# Shared_IoT_Dev.net
KiCad netlist of a schematic drawn in Altium Designer
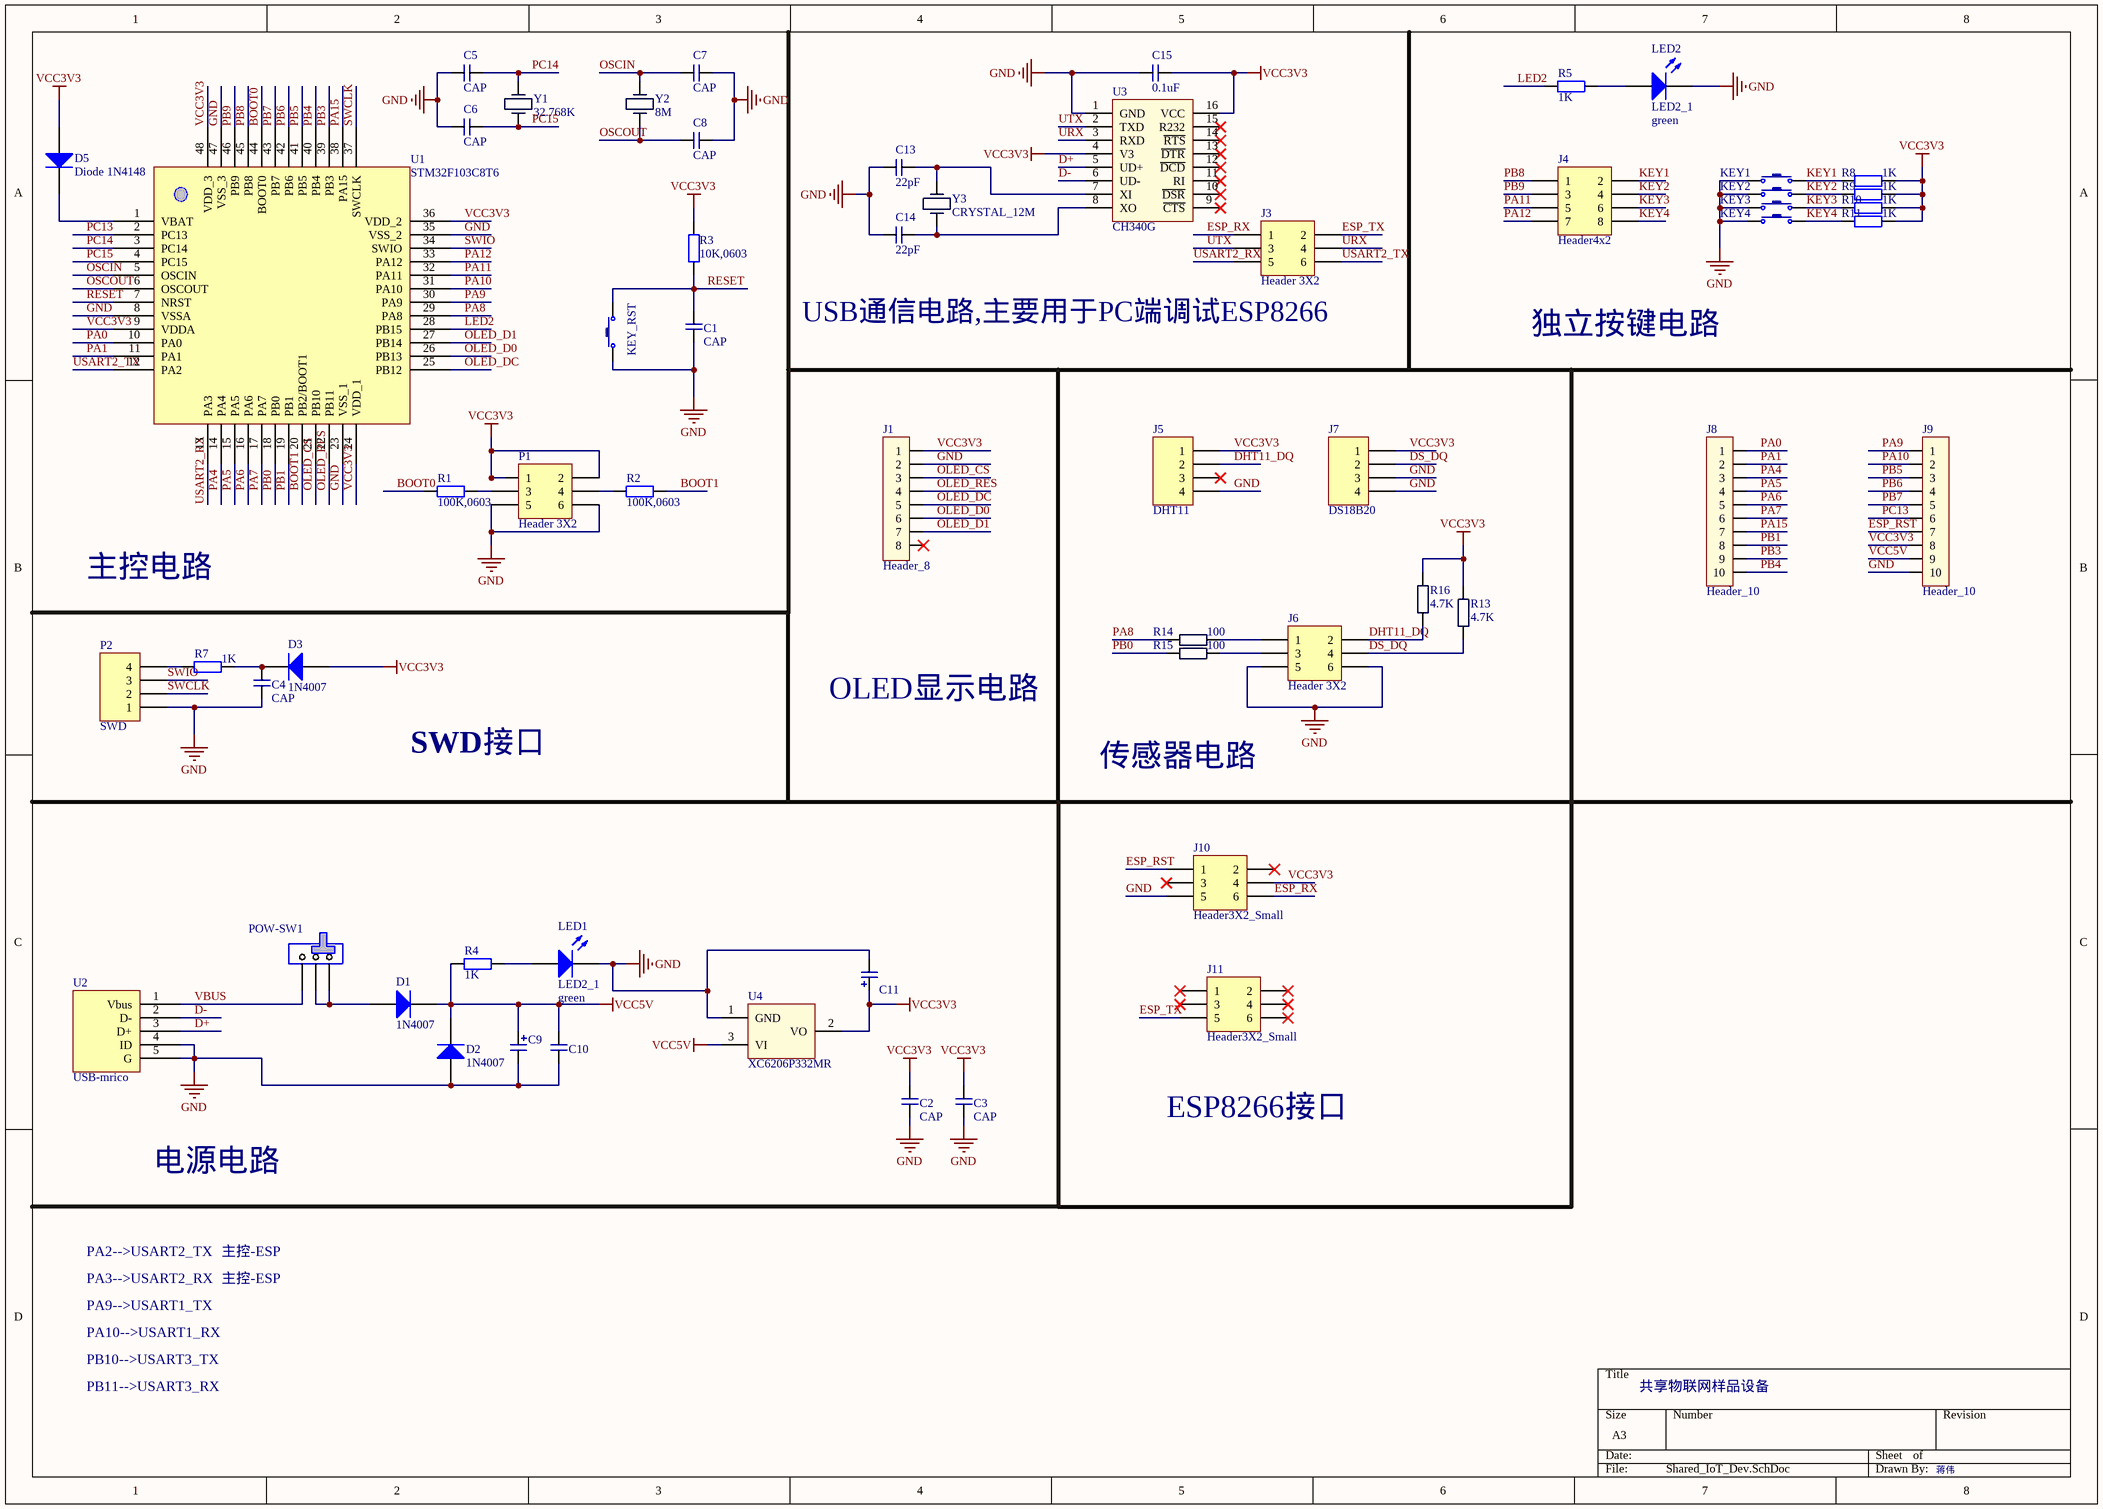
[diagram p0: Shared_IoT_Dev.SchDoc]

(export (version "E")
  (design (tool "Eeschema 10.0.6"))
  (components
    (comp (ref "C1") (value "CAP") (footprint "C0805") (libsource (lib "Arduino") (part "CAP")))
    (comp (ref "C2") (value "CAP") (footprint "C0805") (libsource (lib "Arduino") (part "CAP")))
    (comp (ref "C3") (value "CAP") (footprint "C0805") (libsource (lib "Arduino") (part "CAP")))
    (comp (ref "C4") (value "CAP") (footprint "C0805") (libsource (lib "Arduino") (part "CAP")))
    (comp (ref "C5") (value "CAP") (footprint "C0805") (libsource (lib "Arduino") (part "CAP")))
    (comp (ref "C6") (value "CAP") (footprint "C0805") (libsource (lib "Arduino") (part "CAP")))
    (comp (ref "C7") (value "CAP") (footprint "C0805") (libsource (lib "Arduino") (part "CAP")))
    (comp (ref "C8") (value "CAP") (footprint "C0805") (libsource (lib "Arduino") (part "CAP")))
    (comp (ref "C9") (value "CAP_POL") (footprint "CAP-TH_POL") (libsource (lib "Arduino") (part "CAP_POL")))
    (comp (ref "C10") (value "CAP") (footprint "C0805") (libsource (lib "Arduino") (part "CAP")))
    (comp (ref "C11") (value "CAP_POL") (footprint "CAP-TH_POL") (libsource (lib "Arduino") (part "CAP_POL")))
    (comp (ref "C13")
      (value "22pF")
      (footprint "C0805")
      (description "CAP")
      (libsource (lib "Arduino") (part "CAP"))
    )
    (comp (ref "C14")
      (value "22pF")
      (footprint "C0805")
      (description "CAP")
      (libsource (lib "Arduino") (part "CAP"))
    )
    (comp (ref "C15")
      (value "0.1uF")
      (footprint "C0805")
      (description "CAP")
      (libsource (lib "Arduino") (part "CAP"))
    )
    (comp (ref "D1") (value "1N4007") (footprint "SMA") (libsource (lib "电流测量仪仪主控板原理图7950") (part "DIODE")))
    (comp (ref "D2") (value "1N4007") (footprint "SMA") (libsource (lib "电流测量仪仪主控板原理图7950") (part "DIODE")))
    (comp (ref "D3") (value "1N4007") (footprint "SMA") (libsource (lib "电流测量仪仪主控板原理图7950") (part "DIODE")))
    (comp (ref "D5")
      (value "Diode 1N4148")
      (footprint "SMA")
      (description "High Conductance Fast Diode")
      (fields (field (name "PUBLISHER") "Altium Limited"))
      (libsource (lib "电流测量仪仪主控板原理图7950") (part "Diode 1N4148"))
    )
    (comp (ref "J1")
      (value "Header_8")
      (footprint "HDR-TH_8P-P2.54-V")
      (libsource (lib "Arduino") (part "Header_8"))
    )
    (comp (ref "J3")
      (value "Header 3X2")
      (footprint "HDR2X3")
      (description "Header, 3-Pin, Dual row")
      (fields (field (name "PUBLISHER") "Altium Limited"))
      (libsource (lib "STM32F103C8T6") (part "Header 3X2"))
    )
    (comp (ref "J4")
      (value "Header4x2")
      (footprint "HDR2X4")
      (libsource (lib "STM32F103C8T6") (part "Header4x2"))
    )
    (comp (ref "J5")
      (value "DHT11")
      (footprint "HDR1X4H")
      (description "Header, 4-Pin")
      (fields (field (name "PUBLISHER") "Altium Limited"))
      (libsource (lib "STM32F103C8T6") (part "Header 4"))
    )
    (comp (ref "J6")
      (value "Header 3X2")
      (footprint "HDR2X3")
      (description "Header, 3-Pin, Dual row")
      (fields (field (name "PUBLISHER") "Altium Limited"))
      (libsource (lib "STM32F103C8T6") (part "Header 3X2"))
    )
    (comp (ref "J7")
      (value "DS18B20")
      (footprint "HDR1X4H")
      (description "Header, 4-Pin")
      (fields (field (name "PUBLISHER") "Altium Limited"))
      (libsource (lib "STM32F103C8T6") (part "Header 4"))
    )
    (comp (ref "J8")
      (value "Header_10")
      (footprint "HDR-TH_10P-P2.54-V")
      (libsource (lib "Arduino") (part "Header_10"))
    )
    (comp (ref "J9")
      (value "Header_10")
      (footprint "HDR-TH_10P-P2.54-V")
      (libsource (lib "") (part "Header_10_1"))
    )
    (comp (ref "J10")
      (value "Header3X2_Small")
      (footprint "HDR3X2_Small")
      (libsource (lib "STM32F103C8T6") (part "Header3X2_Small"))
    )
    (comp (ref "J11")
      (value "Header3X2_Small")
      (footprint "HDR3X2_Small")
      (libsource (lib "STM32F103C8T6") (part "Header3X2_Small"))
    )
    (comp (ref "KEY1") (value "KEY") (footprint "KEY-TH_4P") (libsource (lib "Arduino") (part "KEY")))
    (comp (ref "KEY2") (value "KEY") (footprint "KEY-TH_4P") (libsource (lib "Arduino") (part "KEY")))
    (comp (ref "KEY3") (value "KEY") (footprint "KEY-TH_4P") (libsource (lib "Arduino") (part "KEY")))
    (comp (ref "KEY4") (value "KEY") (footprint "KEY-TH_4P") (libsource (lib "Arduino") (part "KEY")))
    (comp (ref "KEY_RST") (value "KEY") (footprint "KEY-TH_4P") (libsource (lib "Arduino") (part "KEY")))
    (comp (ref "LED1")
      (value "LED2_1")
      (footprint "0805C")
      (description "Typical RED, GREEN, YELLOW, AMBER GaAs LED")
      (fields (field (name "ALTIUM_UNNAMED_1") "green") (field (name "PUBLISHER") "Altium Limited"))
      (libsource (lib "电流测量仪仪主控板原理图7950") (part "LED2_1"))
    )
    (comp (ref "LED2")
      (value "LED2_1")
      (footprint "0805C")
      (description "Typical RED, GREEN, YELLOW, AMBER GaAs LED")
      (fields (field (name "ALTIUM_UNNAMED_1") "green") (field (name "PUBLISHER") "Altium Limited"))
      (libsource (lib "电流测量仪仪主控板原理图7950") (part "LED2_1"))
    )
    (comp (ref "P1")
      (value "Header 3X2")
      (footprint "HDR2X3")
      (description "Header, 3-Pin, Dual row")
      (fields (field (name "PUBLISHER") "Altium Limited"))
      (libsource (lib "STM32F103C8T6") (part "Header 3X2"))
    )
    (comp (ref "P2")
      (value "SWD")
      (footprint "HDR1X4H")
      (description "Header, 4-Pin")
      (fields (field (name "PUBLISHER") "Altium Limited"))
      (libsource (lib "") (part "Header 4_1"))
    )
    (comp (ref "POW-SW1")
      (value "Switch")
      (footprint "SW")
      (libsource (lib "电流测量仪仪主控板原理图7950") (part "Swich_On_Off"))
    )
    (comp (ref "R1")
      (value "100K,0603")
      (footprint "R0805")
      (description "Resistor")
      (fields (field (name "PUBLISHER") "Altium Limited"))
      (libsource (lib "") (part "Res2_1"))
    )
    (comp (ref "R2")
      (value "100K,0603")
      (footprint "R0805")
      (description "Resistor")
      (fields (field (name "PUBLISHER") "Altium Limited"))
      (libsource (lib "") (part "Res2_1"))
    )
    (comp (ref "R3")
      (value "10K,0603")
      (footprint "R0805")
      (description "Resistor")
      (fields (field (name "PUBLISHER") "Altium Limited"))
      (libsource (lib "STM32F103C8T6") (part "Res2"))
    )
    (comp (ref "R4")
      (value "1K")
      (footprint "0805R")
      (description "Resistor")
      (fields (field (name "Comment") "Res2") (field (name "PUBLISHER") "Altium Limited"))
      (libsource (lib "电流测量仪仪主控板原理图7950") (part "Res_3"))
    )
    (comp (ref "R5")
      (value "1K")
      (footprint "0805R")
      (description "Resistor")
      (fields (field (name "Comment") "Res2") (field (name "PUBLISHER") "Altium Limited"))
      (libsource (lib "电流测量仪仪主控板原理图7950") (part "Res_3"))
    )
    (comp (ref "R7")
      (value "1K")
      (footprint "0805R")
      (description "Resistor")
      (fields (field (name "Comment") "Res2") (field (name "PUBLISHER") "Altium Limited"))
      (libsource (lib "电流测量仪仪主控板原理图7950") (part "Res2"))
    )
    (comp (ref "R8")
      (value "1K")
      (footprint "0805R")
      (description "Resistor")
      (fields (field (name "Comment") "Res2") (field (name "PUBLISHER") "Altium Limited"))
      (libsource (lib "电流测量仪仪主控板原理图7950") (part "Res_3"))
    )
    (comp (ref "R9")
      (value "1K")
      (footprint "0805R")
      (description "Resistor")
      (fields (field (name "Comment") "Res2") (field (name "PUBLISHER") "Altium Limited"))
      (libsource (lib "电流测量仪仪主控板原理图7950") (part "Res_3"))
    )
    (comp (ref "R10")
      (value "1K")
      (footprint "0805R")
      (description "Resistor")
      (fields (field (name "Comment") "Res2") (field (name "PUBLISHER") "Altium Limited"))
      (libsource (lib "电流测量仪仪主控板原理图7950") (part "Res_3"))
    )
    (comp (ref "R11")
      (value "1K")
      (footprint "0805R")
      (description "Resistor")
      (fields (field (name "Comment") "Res2") (field (name "PUBLISHER") "Altium Limited"))
      (libsource (lib "电流测量仪仪主控板原理图7950") (part "Res_3"))
    )
    (comp (ref "R13")
      (value "4.7K")
      (footprint "R0805")
      (description "RES")
      (libsource (lib "Arduino") (part "RES"))
    )
    (comp (ref "R14")
      (value "100")
      (footprint "R0805")
      (description "RES")
      (libsource (lib "Arduino") (part "RES"))
    )
    (comp (ref "R15")
      (value "100")
      (footprint "R0805")
      (description "RES")
      (libsource (lib "Arduino") (part "RES"))
    )
    (comp (ref "R16")
      (value "4.7K")
      (footprint "R0805")
      (description "RES")
      (libsource (lib "Arduino") (part "RES"))
    )
    (comp (ref "U1")
      (value "STM32F103C8T6")
      (footprint "48P")
      (libsource (lib "STM32F103C8T6") (part "STM32F103C8T6"))
    )
    (comp (ref "U2")
      (value "USB-mrico")
      (footprint "Micro_USB")
      (libsource (lib "STM32F103C8T6") (part "usb-STM"))
    )
    (comp (ref "U3") (value "CH340G") (footprint "CH340G_SOIC") (libsource (lib "Arduino") (part "CH340G")))
    (comp (ref "U4")
      (value "XC6206P332MR")
      (footprint "XC_SOT-23-3")
      (description "XC6206P332MR Power Lower to 3.3v")
      (libsource (lib "Arduino") (part "XC6206P332MR"))
    )
    (comp (ref "Y1")
      (value "32.768K")
      (footprint "CRYSTAL")
      (description "CRYSTAL")
      (libsource (lib "Arduino") (part "CRYSTAL"))
    )
    (comp (ref "Y2")
      (value "8M")
      (footprint "CRYSTAL")
      (description "CRYSTAL")
      (libsource (lib "Arduino") (part "CRYSTAL"))
    )
    (comp (ref "Y3")
      (value "CRYSTAL_12M")
      (footprint "CRYSTAL")
      (description "CRYSTAL")
      (libsource (lib "Arduino") (part "CRYSTAL"))
    )
  )
  (nets
    (net (code "1") (name "/BOOT0") (class "Default")
      (node (ref "R1") (pin "1") (pinfunction "1_1") (pintype "passive"))
      (node (ref "U1") (pin "44") (pinfunction "BOOT0_44") (pintype "passive"))
    )
    (net (code "2") (name "/BOOT1") (class "Default")
      (node (ref "R2") (pin "2") (pinfunction "2_2") (pintype "passive"))
      (node (ref "U1") (pin "20") (pinfunction "PB2/BOOT1_20") (pintype "passive"))
    )
    (net (code "3") (name "/D+") (class "Default")
      (node (ref "U2") (pin "3") (pinfunction "D+_3") (pintype "passive"))
      (node (ref "U3") (pin "5") (pinfunction "UD+_5") (pintype "passive"))
    )
    (net (code "4") (name "/D-") (class "Default")
      (node (ref "U2") (pin "2") (pinfunction "D-_2") (pintype "passive"))
      (node (ref "U3") (pin "6") (pinfunction "UD-_6") (pintype "passive"))
    )
    (net (code "5") (name "/DHT11_DQ") (class "Default")
      (node (ref "J5") (pin "2") (pinfunction "2_2") (pintype "passive"))
      (node (ref "J6") (pin "2") (pinfunction "2_2") (pintype "passive"))
      (node (ref "R16") (pin "1") (pinfunction "1_1") (pintype "passive"))
    )
    (net (code "6") (name "/DS_DQ") (class "Default")
      (node (ref "J6") (pin "4") (pinfunction "4_4") (pintype "passive"))
      (node (ref "J7") (pin "2") (pinfunction "2_2") (pintype "passive"))
      (node (ref "R13") (pin "1") (pinfunction "1_1") (pintype "passive"))
    )
    (net (code "7") (name "/ESP_RST") (class "Default")
      (node (ref "J10") (pin "1") (pinfunction "1_1") (pintype "passive"))
      (node (ref "J9") (pin "7") (pinfunction "7_7") (pintype "passive"))
    )
    (net (code "8") (name "/ESP_RX") (class "Default")
      (node (ref "J10") (pin "6") (pinfunction "6_6") (pintype "passive"))
      (node (ref "J3") (pin "1") (pinfunction "1_1") (pintype "passive"))
    )
    (net (code "9") (name "/ESP_TX") (class "Default")
      (node (ref "J11") (pin "5") (pinfunction "5_5") (pintype "passive"))
      (node (ref "J3") (pin "2") (pinfunction "2_2") (pintype "passive"))
    )
    (net (code "10") (name "/KEY1") (class "Default")
      (node (ref "J4") (pin "2") (pinfunction "2_2") (pintype "passive"))
      (node (ref "KEY1") (pin "3") (pinfunction "3_3") (pintype "passive"))
      (node (ref "R8") (pin "1") (pinfunction "1_1") (pintype "passive"))
    )
    (net (code "11") (name "/KEY2") (class "Default")
      (node (ref "J4") (pin "4") (pinfunction "4_4") (pintype "passive"))
      (node (ref "KEY2") (pin "3") (pinfunction "3_3") (pintype "passive"))
      (node (ref "R9") (pin "1") (pinfunction "1_1") (pintype "passive"))
    )
    (net (code "12") (name "/KEY3") (class "Default")
      (node (ref "J4") (pin "6") (pinfunction "6_6") (pintype "passive"))
      (node (ref "KEY3") (pin "3") (pinfunction "3_3") (pintype "passive"))
      (node (ref "R10") (pin "1") (pinfunction "1_1") (pintype "passive"))
    )
    (net (code "13") (name "/KEY4") (class "Default")
      (node (ref "J4") (pin "8") (pinfunction "8_8") (pintype "passive"))
      (node (ref "KEY4") (pin "3") (pinfunction "3_3") (pintype "passive"))
      (node (ref "R11") (pin "1") (pinfunction "1_1") (pintype "passive"))
    )
    (net (code "14") (name "/LED2") (class "Default")
      (node (ref "R5") (pin "1") (pinfunction "1_1") (pintype "passive"))
      (node (ref "U1") (pin "28") (pinfunction "PB15_28") (pintype "passive"))
    )
    (net (code "15") (name "/OLED_CS") (class "Default")
      (node (ref "J1") (pin "3") (pinfunction "3_3") (pintype "passive"))
      (node (ref "U1") (pin "21") (pinfunction "PB10_21") (pintype "passive"))
    )
    (net (code "16") (name "/OLED_D0") (class "Default")
      (node (ref "J1") (pin "6") (pinfunction "6_6") (pintype "passive"))
      (node (ref "U1") (pin "26") (pinfunction "PB13_26") (pintype "passive"))
    )
    (net (code "17") (name "/OLED_D1") (class "Default")
      (node (ref "J1") (pin "7") (pinfunction "7_7") (pintype "passive"))
      (node (ref "U1") (pin "27") (pinfunction "PB14_27") (pintype "passive"))
    )
    (net (code "18") (name "/OLED_DC") (class "Default")
      (node (ref "J1") (pin "5") (pinfunction "5_5") (pintype "passive"))
      (node (ref "U1") (pin "25") (pinfunction "PB12_25") (pintype "passive"))
    )
    (net (code "19") (name "/OLED_RES") (class "Default")
      (node (ref "J1") (pin "4") (pinfunction "4_4") (pintype "passive"))
      (node (ref "U1") (pin "22") (pinfunction "PB11_22") (pintype "passive"))
    )
    (net (code "20") (name "/OSCIN") (class "Default")
      (node (ref "C7") (pin "1") (pinfunction "1_1") (pintype "passive"))
      (node (ref "U1") (pin "5") (pinfunction "OSCIN_5") (pintype "passive"))
      (node (ref "Y2") (pin "2") (pinfunction "2_2") (pintype "passive"))
    )
    (net (code "21") (name "/OSCOUT") (class "Default")
      (node (ref "C8") (pin "1") (pinfunction "1_1") (pintype "passive"))
      (node (ref "U1") (pin "6") (pinfunction "OSCOUT_6") (pintype "passive"))
      (node (ref "Y2") (pin "1") (pinfunction "1_1") (pintype "passive"))
    )
    (net (code "22") (name "/PA0") (class "Default")
      (node (ref "J8") (pin "1") (pinfunction "1_1") (pintype "passive"))
      (node (ref "U1") (pin "10") (pinfunction "PA0_10") (pintype "passive"))
    )
    (net (code "23") (name "/PA1") (class "Default")
      (node (ref "J8") (pin "2") (pinfunction "2_2") (pintype "passive"))
      (node (ref "U1") (pin "11") (pinfunction "PA1_11") (pintype "passive"))
    )
    (net (code "24") (name "/PA4") (class "Default")
      (node (ref "J8") (pin "3") (pinfunction "3_3") (pintype "passive"))
      (node (ref "U1") (pin "14") (pinfunction "PA4_14") (pintype "passive"))
    )
    (net (code "25") (name "/PA5") (class "Default")
      (node (ref "J8") (pin "4") (pinfunction "4_4") (pintype "passive"))
      (node (ref "U1") (pin "15") (pinfunction "PA5_15") (pintype "passive"))
    )
    (net (code "26") (name "/PA6") (class "Default")
      (node (ref "J8") (pin "5") (pinfunction "5_5") (pintype "passive"))
      (node (ref "U1") (pin "16") (pinfunction "PA6_16") (pintype "passive"))
    )
    (net (code "27") (name "/PA7") (class "Default")
      (node (ref "J8") (pin "6") (pinfunction "6_6") (pintype "passive"))
      (node (ref "U1") (pin "17") (pinfunction "PA7_17") (pintype "passive"))
    )
    (net (code "28") (name "/PA8") (class "Default")
      (node (ref "R14") (pin "2") (pinfunction "2_2") (pintype "passive"))
      (node (ref "U1") (pin "29") (pinfunction "PA8_29") (pintype "passive"))
    )
    (net (code "29") (name "/PA9") (class "Default")
      (node (ref "J9") (pin "1") (pinfunction "1_1") (pintype "passive"))
      (node (ref "U1") (pin "30") (pinfunction "PA9_30") (pintype "passive"))
    )
    (net (code "30") (name "/PA10") (class "Default")
      (node (ref "J9") (pin "2") (pinfunction "2_2") (pintype "passive"))
      (node (ref "U1") (pin "31") (pinfunction "PA10_31") (pintype "passive"))
    )
    (net (code "31") (name "/PA11") (class "Default")
      (node (ref "J4") (pin "5") (pinfunction "5_5") (pintype "passive"))
      (node (ref "U1") (pin "32") (pinfunction "PA11_32") (pintype "passive"))
    )
    (net (code "32") (name "/PA12") (class "Default")
      (node (ref "J4") (pin "7") (pinfunction "7_7") (pintype "passive"))
      (node (ref "U1") (pin "33") (pinfunction "PA12_33") (pintype "passive"))
    )
    (net (code "33") (name "/PA15") (class "Default")
      (node (ref "J8") (pin "7") (pinfunction "7_7") (pintype "passive"))
      (node (ref "U1") (pin "38") (pinfunction "PA15_38") (pintype "passive"))
    )
    (net (code "34") (name "/PB0") (class "Default")
      (node (ref "R15") (pin "2") (pinfunction "2_2") (pintype "passive"))
      (node (ref "U1") (pin "18") (pinfunction "PB0_18") (pintype "passive"))
    )
    (net (code "35") (name "/PB1") (class "Default")
      (node (ref "J8") (pin "8") (pinfunction "8_8") (pintype "passive"))
      (node (ref "U1") (pin "19") (pinfunction "PB1_19") (pintype "passive"))
    )
    (net (code "36") (name "/PB3") (class "Default")
      (node (ref "J8") (pin "9") (pinfunction "9_9") (pintype "passive"))
      (node (ref "U1") (pin "39") (pinfunction "PB3_39") (pintype "passive"))
    )
    (net (code "37") (name "/PB4") (class "Default")
      (node (ref "J8") (pin "10") (pinfunction "10_10") (pintype "passive"))
      (node (ref "U1") (pin "40") (pinfunction "PB4_40") (pintype "passive"))
    )
    (net (code "38") (name "/PB5") (class "Default")
      (node (ref "J9") (pin "3") (pinfunction "3_3") (pintype "passive"))
      (node (ref "U1") (pin "41") (pinfunction "PB5_41") (pintype "passive"))
    )
    (net (code "39") (name "/PB6") (class "Default")
      (node (ref "J9") (pin "4") (pinfunction "4_4") (pintype "passive"))
      (node (ref "U1") (pin "42") (pinfunction "PB6_42") (pintype "passive"))
    )
    (net (code "40") (name "/PB7") (class "Default")
      (node (ref "J9") (pin "5") (pinfunction "5_5") (pintype "passive"))
      (node (ref "U1") (pin "43") (pinfunction "PB7_43") (pintype "passive"))
    )
    (net (code "41") (name "/PB8") (class "Default")
      (node (ref "J4") (pin "1") (pinfunction "1_1") (pintype "passive"))
      (node (ref "U1") (pin "45") (pinfunction "PB8_45") (pintype "passive"))
    )
    (net (code "42") (name "/PB9") (class "Default")
      (node (ref "J4") (pin "3") (pinfunction "3_3") (pintype "passive"))
      (node (ref "U1") (pin "46") (pinfunction "PB9_46") (pintype "passive"))
    )
    (net (code "43") (name "/PC13") (class "Default")
      (node (ref "J9") (pin "6") (pinfunction "6_6") (pintype "passive"))
      (node (ref "U1") (pin "2") (pinfunction "PC13_2") (pintype "passive"))
    )
    (net (code "44") (name "/PC14") (class "Default")
      (node (ref "C5") (pin "2") (pinfunction "2_2") (pintype "passive"))
      (node (ref "U1") (pin "3") (pinfunction "PC14_3") (pintype "passive"))
      (node (ref "Y1") (pin "2") (pinfunction "2_2") (pintype "passive"))
    )
    (net (code "45") (name "/PC15") (class "Default")
      (node (ref "C6") (pin "2") (pinfunction "2_2") (pintype "passive"))
      (node (ref "U1") (pin "4") (pinfunction "PC15_4") (pintype "passive"))
      (node (ref "Y1") (pin "1") (pinfunction "1_1") (pintype "passive"))
    )
    (net (code "46") (name "/RESET") (class "Default")
      (node (ref "C1") (pin "1") (pinfunction "1_1") (pintype "passive"))
      (node (ref "KEY_RST") (pin "3") (pinfunction "3_3") (pintype "passive"))
      (node (ref "R3") (pin "1") (pinfunction "1_1") (pintype "passive"))
      (node (ref "U1") (pin "7") (pinfunction "NRST_7") (pintype "passive"))
    )
    (net (code "47") (name "/SWCLK") (class "Default")
      (node (ref "P2") (pin "2") (pinfunction "2_2") (pintype "passive"))
      (node (ref "U1") (pin "37") (pinfunction "SWCLK_37") (pintype "passive"))
    )
    (net (code "48") (name "/SWIO") (class "Default")
      (node (ref "P2") (pin "3") (pinfunction "3_3") (pintype "passive"))
      (node (ref "U1") (pin "34") (pinfunction "SWIO_34") (pintype "passive"))
    )
    (net (code "49") (name "/URX") (class "Default")
      (node (ref "J3") (pin "4") (pinfunction "4_4") (pintype "passive"))
      (node (ref "U3") (pin "3") (pinfunction "RXD_3") (pintype "passive"))
    )
    (net (code "50") (name "/USART2_RX") (class "Default")
      (node (ref "J3") (pin "5") (pinfunction "5_5") (pintype "passive"))
      (node (ref "U1") (pin "13") (pinfunction "PA3_13") (pintype "passive"))
    )
    (net (code "51") (name "/USART2_TX") (class "Default")
      (node (ref "J3") (pin "6") (pinfunction "6_6") (pintype "passive"))
      (node (ref "U1") (pin "12") (pinfunction "PA2_12") (pintype "passive"))
    )
    (net (code "52") (name "/UTX") (class "Default")
      (node (ref "J3") (pin "3") (pinfunction "3_3") (pintype "passive"))
      (node (ref "U3") (pin "2") (pinfunction "TXD_2") (pintype "passive"))
    )
    (net (code "53") (name "/VBUS") (class "Default")
      (node (ref "POW-SW1") (pin "1") (pinfunction "1_1") (pintype "passive"))
      (node (ref "U2") (pin "1") (pinfunction "Vbus_1") (pintype "passive"))
    )
    (net (code "54") (name "GND") (class "Default")
      (node (ref "C1") (pin "2") (pinfunction "2_2") (pintype "passive"))
      (node (ref "C10") (pin "1") (pinfunction "1_1") (pintype "passive"))
      (node (ref "C11") (pin "2") (pinfunction "2_2") (pintype "passive"))
      (node (ref "C13") (pin "2") (pinfunction "2_2") (pintype "passive"))
      (node (ref "C14") (pin "2") (pinfunction "2_2") (pintype "passive"))
      (node (ref "C15") (pin "2") (pinfunction "2_2") (pintype "passive"))
      (node (ref "C2") (pin "2") (pinfunction "2_2") (pintype "passive"))
      (node (ref "C3") (pin "2") (pinfunction "2_2") (pintype "passive"))
      (node (ref "C4") (pin "2") (pinfunction "2_2") (pintype "passive"))
      (node (ref "C5") (pin "1") (pinfunction "1_1") (pintype "passive"))
      (node (ref "C6") (pin "1") (pinfunction "1_1") (pintype "passive"))
      (node (ref "C7") (pin "2") (pinfunction "2_2") (pintype "passive"))
      (node (ref "C8") (pin "2") (pinfunction "2_2") (pintype "passive"))
      (node (ref "C9") (pin "2") (pinfunction "2_2") (pintype "passive"))
      (node (ref "D2") (pin "1") (pinfunction "A_1") (pintype "passive"))
      (node (ref "J1") (pin "2") (pinfunction "2_2") (pintype "passive"))
      (node (ref "J10") (pin "5") (pinfunction "5_5") (pintype "passive"))
      (node (ref "J5") (pin "4") (pinfunction "4_4") (pintype "passive"))
      (node (ref "J6") (pin "5") (pinfunction "5_5") (pintype "passive"))
      (node (ref "J6") (pin "6") (pinfunction "6_6") (pintype "passive"))
      (node (ref "J7") (pin "3") (pinfunction "3_3") (pintype "passive"))
      (node (ref "J7") (pin "4") (pinfunction "4_4") (pintype "passive"))
      (node (ref "J9") (pin "10") (pinfunction "10_10") (pintype "passive"))
      (node (ref "KEY1") (pin "1") (pinfunction "1_1") (pintype "passive"))
      (node (ref "KEY2") (pin "1") (pinfunction "1_1") (pintype "passive"))
      (node (ref "KEY3") (pin "1") (pinfunction "1_1") (pintype "passive"))
      (node (ref "KEY4") (pin "1") (pinfunction "1_1") (pintype "passive"))
      (node (ref "KEY_RST") (pin "1") (pinfunction "1_1") (pintype "passive"))
      (node (ref "LED1") (pin "2") (pinfunction "K_2") (pintype "passive"))
      (node (ref "LED2") (pin "2") (pinfunction "K_2") (pintype "passive"))
      (node (ref "P1") (pin "5") (pinfunction "5_5") (pintype "passive"))
      (node (ref "P1") (pin "6") (pinfunction "6_6") (pintype "passive"))
      (node (ref "P2") (pin "1") (pinfunction "1_1") (pintype "passive"))
      (node (ref "U1") (pin "23") (pinfunction "VSS_1_23") (pintype "passive"))
      (node (ref "U1") (pin "35") (pinfunction "VSS_2_35") (pintype "passive"))
      (node (ref "U1") (pin "47") (pinfunction "VSS_3_47") (pintype "passive"))
      (node (ref "U1") (pin "8") (pinfunction "VSSA_8") (pintype "passive"))
      (node (ref "U2") (pin "4") (pinfunction "ID_4") (pintype "passive"))
      (node (ref "U2") (pin "5") (pinfunction "G_5") (pintype "passive"))
      (node (ref "U3") (pin "1") (pinfunction "GND_1") (pintype "passive"))
      (node (ref "U4") (pin "1") (pinfunction "GND_1") (pintype "passive"))
    )
    (net (code "55") (name "Net-(D1-A)") (class "Default")
      (node (ref "D1") (pin "1") (pinfunction "A_1") (pintype "passive"))
      (node (ref "POW-SW1") (pin "2") (pinfunction "2_2") (pintype "passive"))
      (node (ref "POW-SW1") (pin "3") (pinfunction "3_3") (pintype "passive"))
    )
    (net (code "56") (name "Net-(D3-K)") (class "Default")
      (node (ref "C4") (pin "1") (pinfunction "1_1") (pintype "passive"))
      (node (ref "D3") (pin "2") (pinfunction "K_2") (pintype "passive"))
      (node (ref "R7") (pin "2") (pinfunction "2_2") (pintype "passive"))
    )
    (net (code "57") (name "Net-(D5-K)") (class "Default")
      (node (ref "D5") (pin "2") (pinfunction "K_2") (pintype "passive"))
      (node (ref "U1") (pin "1") (pinfunction "VBAT_1") (pintype "passive"))
    )
    (net (code "58") (name "Net-(J6-Pad1)") (class "Default")
      (node (ref "J6") (pin "1") (pinfunction "1_1") (pintype "passive"))
      (node (ref "R14") (pin "1") (pinfunction "1_1") (pintype "passive"))
    )
    (net (code "59") (name "Net-(J6-Pad3)") (class "Default")
      (node (ref "J6") (pin "3") (pinfunction "3_3") (pintype "passive"))
      (node (ref "R15") (pin "1") (pinfunction "1_1") (pintype "passive"))
    )
    (net (code "60") (name "Net-(LED1-A)") (class "Default")
      (node (ref "LED1") (pin "1") (pinfunction "A_1") (pintype "passive"))
      (node (ref "R4") (pin "2") (pinfunction "2_2") (pintype "passive"))
    )
    (net (code "61") (name "Net-(LED2-A)") (class "Default")
      (node (ref "LED2") (pin "1") (pinfunction "A_1") (pintype "passive"))
      (node (ref "R5") (pin "2") (pinfunction "2_2") (pintype "passive"))
    )
    (net (code "62") (name "Net-(P1-Pad3)") (class "Default")
      (node (ref "P1") (pin "3") (pinfunction "3_3") (pintype "passive"))
      (node (ref "R1") (pin "2") (pinfunction "2_2") (pintype "passive"))
    )
    (net (code "63") (name "Net-(P1-Pad4)") (class "Default")
      (node (ref "P1") (pin "4") (pinfunction "4_4") (pintype "passive"))
      (node (ref "R2") (pin "1") (pinfunction "1_1") (pintype "passive"))
    )
    (net (code "64") (name "Net-(P2-Pad4)") (class "Default")
      (node (ref "P2") (pin "4") (pinfunction "4_4") (pintype "passive"))
      (node (ref "R7") (pin "1") (pinfunction "1_1") (pintype "passive"))
    )
    (net (code "65") (name "Net-(U3-XI)") (class "Default")
      (node (ref "C13") (pin "1") (pinfunction "1_1") (pintype "passive"))
      (node (ref "U3") (pin "7") (pinfunction "XI_7") (pintype "passive"))
      (node (ref "Y3") (pin "2") (pinfunction "2_2") (pintype "passive"))
    )
    (net (code "66") (name "Net-(U3-XO)") (class "Default")
      (node (ref "C14") (pin "1") (pinfunction "1_1") (pintype "passive"))
      (node (ref "U3") (pin "8") (pinfunction "XO_8") (pintype "passive"))
      (node (ref "Y3") (pin "1") (pinfunction "1_1") (pintype "passive"))
    )
    (net (code "67") (name "VCC3V3") (class "Default")
      (node (ref "C11") (pin "1") (pinfunction "1_1") (pintype "passive"))
      (node (ref "C15") (pin "1") (pinfunction "1_1") (pintype "passive"))
      (node (ref "C2") (pin "1") (pinfunction "1_1") (pintype "passive"))
      (node (ref "C3") (pin "1") (pinfunction "1_1") (pintype "passive"))
      (node (ref "D3") (pin "1") (pinfunction "A_1") (pintype "passive"))
      (node (ref "D5") (pin "1") (pinfunction "A_1") (pintype "passive"))
      (node (ref "J1") (pin "1") (pinfunction "1_1") (pintype "passive"))
      (node (ref "J10") (pin "4") (pinfunction "4_4") (pintype "passive"))
      (node (ref "J5") (pin "1") (pinfunction "1_1") (pintype "passive"))
      (node (ref "J7") (pin "1") (pinfunction "1_1") (pintype "passive"))
      (node (ref "J9") (pin "8") (pinfunction "8_8") (pintype "passive"))
      (node (ref "P1") (pin "1") (pinfunction "1_1") (pintype "passive"))
      (node (ref "P1") (pin "2") (pinfunction "2_2") (pintype "passive"))
      (node (ref "R10") (pin "2") (pinfunction "2_2") (pintype "passive"))
      (node (ref "R11") (pin "2") (pinfunction "2_2") (pintype "passive"))
      (node (ref "R13") (pin "2") (pinfunction "2_2") (pintype "passive"))
      (node (ref "R16") (pin "2") (pinfunction "2_2") (pintype "passive"))
      (node (ref "R3") (pin "2") (pinfunction "2_2") (pintype "passive"))
      (node (ref "R8") (pin "2") (pinfunction "2_2") (pintype "passive"))
      (node (ref "R9") (pin "2") (pinfunction "2_2") (pintype "passive"))
      (node (ref "U1") (pin "24") (pinfunction "VDD_1_24") (pintype "passive"))
      (node (ref "U1") (pin "36") (pinfunction "VDD_2_36") (pintype "passive"))
      (node (ref "U1") (pin "48") (pinfunction "VDD_3_48") (pintype "passive"))
      (node (ref "U1") (pin "9") (pinfunction "VDDA_9") (pintype "passive"))
      (node (ref "U3") (pin "16") (pinfunction "VCC_16") (pintype "passive"))
      (node (ref "U3") (pin "4") (pinfunction "V3_4") (pintype "passive"))
      (node (ref "U4") (pin "2") (pinfunction "VO_2") (pintype "passive"))
    )
    (net (code "68") (name "VCC5V") (class "Default")
      (node (ref "C10") (pin "2") (pinfunction "2_2") (pintype "passive"))
      (node (ref "C9") (pin "1") (pinfunction "1_1") (pintype "passive"))
      (node (ref "D1") (pin "2") (pinfunction "K_2") (pintype "passive"))
      (node (ref "D2") (pin "2") (pinfunction "K_2") (pintype "passive"))
      (node (ref "J9") (pin "9") (pinfunction "9_9") (pintype "passive"))
      (node (ref "R4") (pin "1") (pinfunction "1_1") (pintype "passive"))
      (node (ref "U4") (pin "3") (pinfunction "VI_3") (pintype "passive"))
    )
    (net (code "69") (name "unconnected-(J1-Pad8)") (class "Default")
      (node (ref "J1") (pin "8") (pinfunction "8_8") (pintype "passive+no_connect"))
    )
    (net (code "70") (name "unconnected-(J5-Pad3)") (class "Default")
      (node (ref "J5") (pin "3") (pinfunction "3_3") (pintype "passive+no_connect"))
    )
    (net (code "71") (name "unconnected-(J10-Pad2)") (class "Default")
      (node (ref "J10") (pin "2") (pinfunction "2_2") (pintype "passive+no_connect"))
    )
    (net (code "72") (name "unconnected-(J10-Pad3)") (class "Default")
      (node (ref "J10") (pin "3") (pinfunction "3_3") (pintype "passive+no_connect"))
    )
    (net (code "73") (name "unconnected-(J11-Pad1)") (class "Default")
      (node (ref "J11") (pin "1") (pinfunction "1_1") (pintype "passive+no_connect"))
    )
    (net (code "74") (name "unconnected-(J11-Pad2)") (class "Default")
      (node (ref "J11") (pin "2") (pinfunction "2_2") (pintype "passive+no_connect"))
    )
    (net (code "75") (name "unconnected-(J11-Pad3)") (class "Default")
      (node (ref "J11") (pin "3") (pinfunction "3_3") (pintype "passive+no_connect"))
    )
    (net (code "76") (name "unconnected-(J11-Pad4)") (class "Default")
      (node (ref "J11") (pin "4") (pinfunction "4_4") (pintype "passive+no_connect"))
    )
    (net (code "77") (name "unconnected-(J11-Pad6)") (class "Default")
      (node (ref "J11") (pin "6") (pinfunction "6_6") (pintype "passive+no_connect"))
    )
    (net (code "78") (name "unconnected-(KEY1-Pad2)") (class "Default")
      (node (ref "KEY1") (pin "2") (pinfunction "2_2") (pintype "passive"))
    )
    (net (code "79") (name "unconnected-(KEY1-Pad4)") (class "Default")
      (node (ref "KEY1") (pin "4") (pinfunction "4_4") (pintype "passive"))
    )
    (net (code "80") (name "unconnected-(KEY2-Pad2)") (class "Default")
      (node (ref "KEY2") (pin "2") (pinfunction "2_2") (pintype "passive"))
    )
    (net (code "81") (name "unconnected-(KEY2-Pad4)") (class "Default")
      (node (ref "KEY2") (pin "4") (pinfunction "4_4") (pintype "passive"))
    )
    (net (code "82") (name "unconnected-(KEY3-Pad2)") (class "Default")
      (node (ref "KEY3") (pin "2") (pinfunction "2_2") (pintype "passive"))
    )
    (net (code "83") (name "unconnected-(KEY3-Pad4)") (class "Default")
      (node (ref "KEY3") (pin "4") (pinfunction "4_4") (pintype "passive"))
    )
    (net (code "84") (name "unconnected-(KEY4-Pad2)") (class "Default")
      (node (ref "KEY4") (pin "2") (pinfunction "2_2") (pintype "passive"))
    )
    (net (code "85") (name "unconnected-(KEY4-Pad4)") (class "Default")
      (node (ref "KEY4") (pin "4") (pinfunction "4_4") (pintype "passive"))
    )
    (net (code "86") (name "unconnected-(KEY_RST-Pad2)") (class "Default")
      (node (ref "KEY_RST") (pin "2") (pinfunction "2_2") (pintype "passive"))
    )
    (net (code "87") (name "unconnected-(KEY_RST-Pad4)") (class "Default")
      (node (ref "KEY_RST") (pin "4") (pinfunction "4_4") (pintype "passive"))
    )
    (net (code "88") (name "unconnected-(U3-R232-Pad15)") (class "Default")
      (node (ref "U3") (pin "15") (pinfunction "R232_15") (pintype "passive+no_connect"))
    )
    (net (code "89") (name "unconnected-(U3-RI-Pad11)") (class "Default")
      (node (ref "U3") (pin "11") (pinfunction "RI_11") (pintype "passive+no_connect"))
    )
    (net (code "90") (name "unconnected-(U3-~{CTS}-Pad9)") (class "Default")
      (node (ref "U3") (pin "9") (pinfunction "~{CTS}_9") (pintype "passive+no_connect"))
    )
    (net (code "91") (name "unconnected-(U3-~{DCD}-Pad12)") (class "Default")
      (node (ref "U3") (pin "12") (pinfunction "~{DCD}_12") (pintype "passive+no_connect"))
    )
    (net (code "92") (name "unconnected-(U3-~{DSR}-Pad10)") (class "Default")
      (node (ref "U3") (pin "10") (pinfunction "~{DSR}_10") (pintype "passive+no_connect"))
    )
    (net (code "93") (name "unconnected-(U3-~{DTR}-Pad13)") (class "Default")
      (node (ref "U3") (pin "13") (pinfunction "~{DTR}_13") (pintype "passive+no_connect"))
    )
    (net (code "94") (name "unconnected-(U3-~{RTS}-Pad14)") (class "Default")
      (node (ref "U3") (pin "14") (pinfunction "~{RTS}_14") (pintype "passive+no_connect"))
    )
  )
)
